# Power_Protection.net
KiCad netlist of a schematic drawn in Altium Designer
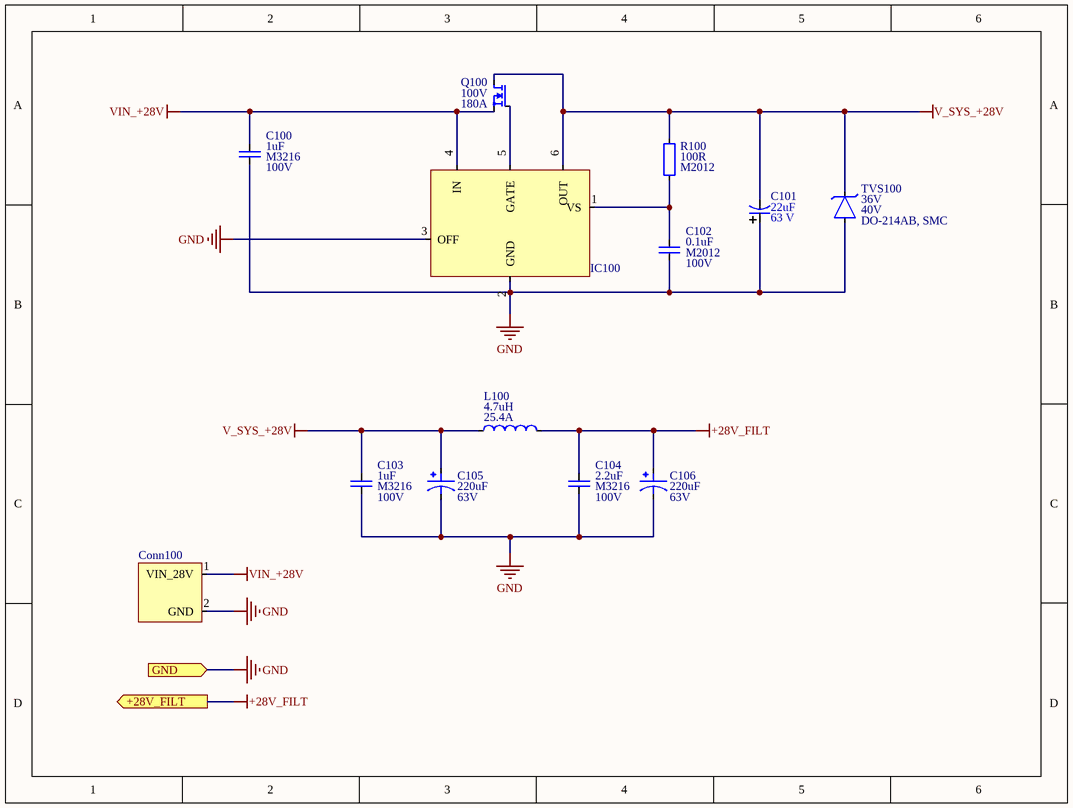
[diagram p0: Power_Protection.SchDoc]

(export (version "E")
  (design (tool "Eeschema 10.0.6"))
  (components
    (comp (ref "C100")
      (value "1uF")
      (footprint "Capacitor_Seramic_M3216_I1206")
      (description "Cap, Cer, 1uF, 100V, M3216")
      (fields
        (field (name "TOLERANCE") "±10%")
        (field (name "MANUFACTURER PART NUMBER") "C3216X7R2A105K160AA")
        (field (name "PACKAGE") "M3216")
        (field (name "RATED VOLTAGE") "100V")
      )
      (libsource (lib "Capacitor") (part "Capacitor_Seramic"))
    )
    (comp (ref "C101")
      (value "22uF")
      (footprint "PCAP_EEHZ_D8_PAN")
      (description "Cap, Aluminum")
      (fields
        (field (name "TOLERANCE") "±20%")
        (field (name "MANUFACTURER") "Panasonic")
        (field (name "RATED VOLTAGE") "63 V")
      )
      (libsource (lib "Capacitor") (part "Capacitor_Aluminum"))
    )
    (comp (ref "C102")
      (value "0.1uF")
      (footprint "Capacitor_Seramic_M2012_I0805")
      (description "Cap, Cer, 0.1uF, 100V, M2012")
      (fields
        (field (name "TOLERANCE") "±10%")
        (field (name "MANUFACTURER PART NUMBER") "C2012X7R2A104K125AA")
        (field (name "PACKAGE") "M2012")
        (field (name "RATED VOLTAGE") "100V")
      )
      (libsource (lib "Capacitor") (part "Capacitor_Seramic"))
    )
    (comp (ref "C103")
      (value "1uF")
      (footprint "Capacitor_Seramic_M3216_I1206")
      (description "Cap, Cer, 1uF, 100V, M3216")
      (fields
        (field (name "TOLERANCE") "±10%")
        (field (name "MANUFACTURER PART NUMBER") "C3216X7R2A105K160AA")
        (field (name "PACKAGE") "M3216")
        (field (name "RATED VOLTAGE") "100V")
      )
      (libsource (lib "Capacitor") (part "Capacitor_Seramic"))
    )
    (comp (ref "C104")
      (value "2.2uF")
      (footprint "Capacitor_Seramic_M3216_I1206")
      (description "Cap, Cer, 2.2uF, 100V, M3216")
      (fields
        (field (name "TOLERANCE") "±10%")
        (field (name "MANUFACTURER PART NUMBER") "AC1206KKX7R0BB225")
        (field (name "PACKAGE") "M3216")
        (field (name "RATED VOLTAGE") "100V")
      )
      (libsource (lib "Capacitor") (part "Capacitor_Seramic"))
    )
    (comp (ref "C105")
      (value "220uF")
      (footprint "Capacitor_Aluminum_TH")
      (description "220F 63V Aluminum Electrolytic Capacitors Radial, Can 10000 Hrs @ 105C")
      (fields
        (field (name "MANUFACTURER") "Panasonic Electronic Components")
        (field (name "MANUFACTURER PART NUMBER") "EEU-FR1J221L")
        (field (name "RATED VOLTAGE") "63V")
      )
      (libsource (lib "Capacitor") (part "Capacitor_Aluminum_TH"))
    )
    (comp (ref "C106")
      (value "220uF")
      (footprint "Capacitor_Aluminum_TH")
      (description "220F 63V Aluminum Electrolytic Capacitors Radial, Can 10000 Hrs @ 105C")
      (fields
        (field (name "MANUFACTURER") "Panasonic Electronic Components")
        (field (name "MANUFACTURER PART NUMBER") "EEU-FR1J221L")
        (field (name "RATED VOLTAGE") "63V")
      )
      (libsource (lib "Capacitor") (part "Capacitor_Aluminum_TH"))
    )
    (comp (ref "Conn100")
      (value "KF128-2P")
      (footprint "Connector - KF128-5.08-2P")
      (libsource (lib "Connector - Header") (part "Connector - 2P"))
    )
    (comp (ref "IC100")
      (value "Diodes, LM5050MK-1")
      (footprint "SOT-23-6Pin")
      (description "IC, Power, DC-DC, TI, LM5050MK-1")
      (fields
        (field (name "MANUFACTURER") "Texas Instruments")
        (field (name "MANUFACTURER PART NUMBER") "LM5050MK-1/NOPB")
        (field (name "COMPONENTLINK1URL") "C:\\Users\\User\\OneDrive - Karadeniz Teknik University\\Masaüstü\\pcb\\kütüphane\\Datasheet\\lm5050-1.pdf")
      )
      (libsource (lib "IC - Power - DC-DC") (part "Diodes, LM5050MK-1"))
    )
    (comp (ref "L100")
      (value "4.7uH")
      (footprint "Coilcraft - XAL1010-472MED")
      (description "Inductor")
      (fields
        (field (name "MANUFACTURER PART NUMBER") "XAL1010-472MED")
        (field (name "MANUFACTURER") "Coilcraft")
        (field (name "SATURATION CURRENT") "25.4A")
      )
      (libsource (lib "Inductor") (part "Inductor"))
    )
    (comp (ref "Q100")
      (value "Mosfet, N-Channel - IPB017N10N5")
      (footprint "TO263-7, Mosfet - Type 1")
      (fields
        (field (name "MANUFACTURER PART NUMBER") "IPB017N10N5ATMA1")
        (field (name "MANUFACTURER") "Infineon Technologies")
        (field (name "CURRENT") "180A")
        (field (name "VOLTAGE") "100V")
        (field (name "COMPONENTLINK1URL") "C:\\Users\\User\\OneDrive - Karadeniz Teknik University\\Masaüstü\\pcb\\kütüphane\\Datasheet\\infineon-ipb017n10n5-datasheet-en.pdf")
      )
      (libsource (lib "Transistor") (part "Mosfet, N-Channel - IPB017N10N5"))
    )
    (comp (ref "R100")
      (value "100R")
      (footprint "Resistor_SMD_M2012_I0805")
      (description "Res, 100R, 1%, M2012")
      (fields
        (field (name "MANUFACTURER") "Yageo")
        (field (name "MANUFACTURER PART NUMBER") "RC0805FR-07100RL")
        (field (name "PACKAGE") "M2012")
      )
      (libsource (lib "Resistor") (part "Resistor"))
    )
    (comp (ref "TVS100")
      (value "Diode_Tvs")
      (footprint "Diode_SMC_DO-214AB")
      (fields
        (field (name "MANUFACTURER PART NUMBER") "5.0SMDJ36A")
        (field (name "MANUFACTURER") "Littelfuse Inc.")
        (field (name "VOLTAGE, BREAK DOWN") "40V")
        (field (name "VOLTAGE, STAND OFF") "36V")
        (field (name "PACKAGE") "DO-214AB, SMC")
        (field (name "COMPONENTLINK1URL") "C:\\Users\\User\\OneDrive - Karadeniz Teknik University\\Masaüstü\\pcb\\kütüphane\\Datasheet\\Littelfuse-TVS-Diode-5-0SMDJ-Datasheet-20250624.pdf")
      )
      (libsource (lib "Diode") (part "Diode_Tvs"))
    )
  )
  (nets
    (net (code "1") (name "+28V_FILT") (class "Default")
      (node (ref "C104") (pin "1") (pinfunction "1_1") (pintype "passive"))
      (node (ref "C106") (pin "P") (pinfunction "P_P") (pintype "passive"))
      (node (ref "L100") (pin "1") (pinfunction "1_1") (pintype "passive"))
    )
    (net (code "2") (name "GND") (class "Default")
      (node (ref "C100") (pin "2") (pinfunction "2_2") (pintype "passive"))
      (node (ref "C101") (pin "1") (pinfunction "1_1") (pintype "passive"))
      (node (ref "C102") (pin "2") (pinfunction "2_2") (pintype "passive"))
      (node (ref "C103") (pin "2") (pinfunction "2_2") (pintype "passive"))
      (node (ref "C104") (pin "2") (pinfunction "2_2") (pintype "passive"))
      (node (ref "C105") (pin "N") (pinfunction "N_N") (pintype "passive"))
      (node (ref "C106") (pin "N") (pinfunction "N_N") (pintype "passive"))
      (node (ref "Conn100") (pin "2") (pinfunction "GND_2") (pintype "passive"))
      (node (ref "IC100") (pin "2") (pinfunction "GND_2") (pintype "passive"))
      (node (ref "IC100") (pin "3") (pinfunction "OFF_3") (pintype "passive"))
      (node (ref "TVS100") (pin "A") (pinfunction "A_A") (pintype "passive"))
    )
    (net (code "3") (name "Net-(IC100-GATE)") (class "Default")
      (node (ref "IC100") (pin "5") (pinfunction "GATE_5") (pintype "passive"))
      (node (ref "Q100") (pin "G") (pinfunction "G_G") (pintype "passive"))
    )
    (net (code "4") (name "Net-(IC100-VS)") (class "Default")
      (node (ref "C102") (pin "1") (pinfunction "1_1") (pintype "passive"))
      (node (ref "IC100") (pin "1") (pinfunction "VS_1") (pintype "passive"))
      (node (ref "R100") (pin "2") (pinfunction "2_2") (pintype "passive"))
    )
    (net (code "5") (name "VIN_+28V") (class "Default")
      (node (ref "C100") (pin "1") (pinfunction "1_1") (pintype "passive"))
      (node (ref "Conn100") (pin "1") (pinfunction "VIN_28V_1") (pintype "passive"))
      (node (ref "IC100") (pin "4") (pinfunction "IN_4") (pintype "passive"))
      (node (ref "Q100") (pin "S") (pinfunction "S_S") (pintype "passive"))
    )
    (net (code "6") (name "V_SYS_+28V") (class "Default")
      (node (ref "C101") (pin "2") (pinfunction "2_2") (pintype "passive"))
      (node (ref "C103") (pin "1") (pinfunction "1_1") (pintype "passive"))
      (node (ref "C105") (pin "P") (pinfunction "P_P") (pintype "passive"))
      (node (ref "IC100") (pin "6") (pinfunction "OUT_6") (pintype "passive"))
      (node (ref "L100") (pin "2") (pinfunction "2_2") (pintype "passive"))
      (node (ref "Q100") (pin "D") (pinfunction "D_D") (pintype "passive"))
      (node (ref "R100") (pin "1") (pinfunction "1_1") (pintype "passive"))
      (node (ref "TVS100") (pin "K") (pinfunction "K_K") (pintype "passive"))
    )
  )
)
